# Charger_Interface_-_Relay_Controls.net
KiCad netlist of a schematic drawn in Altium Designer
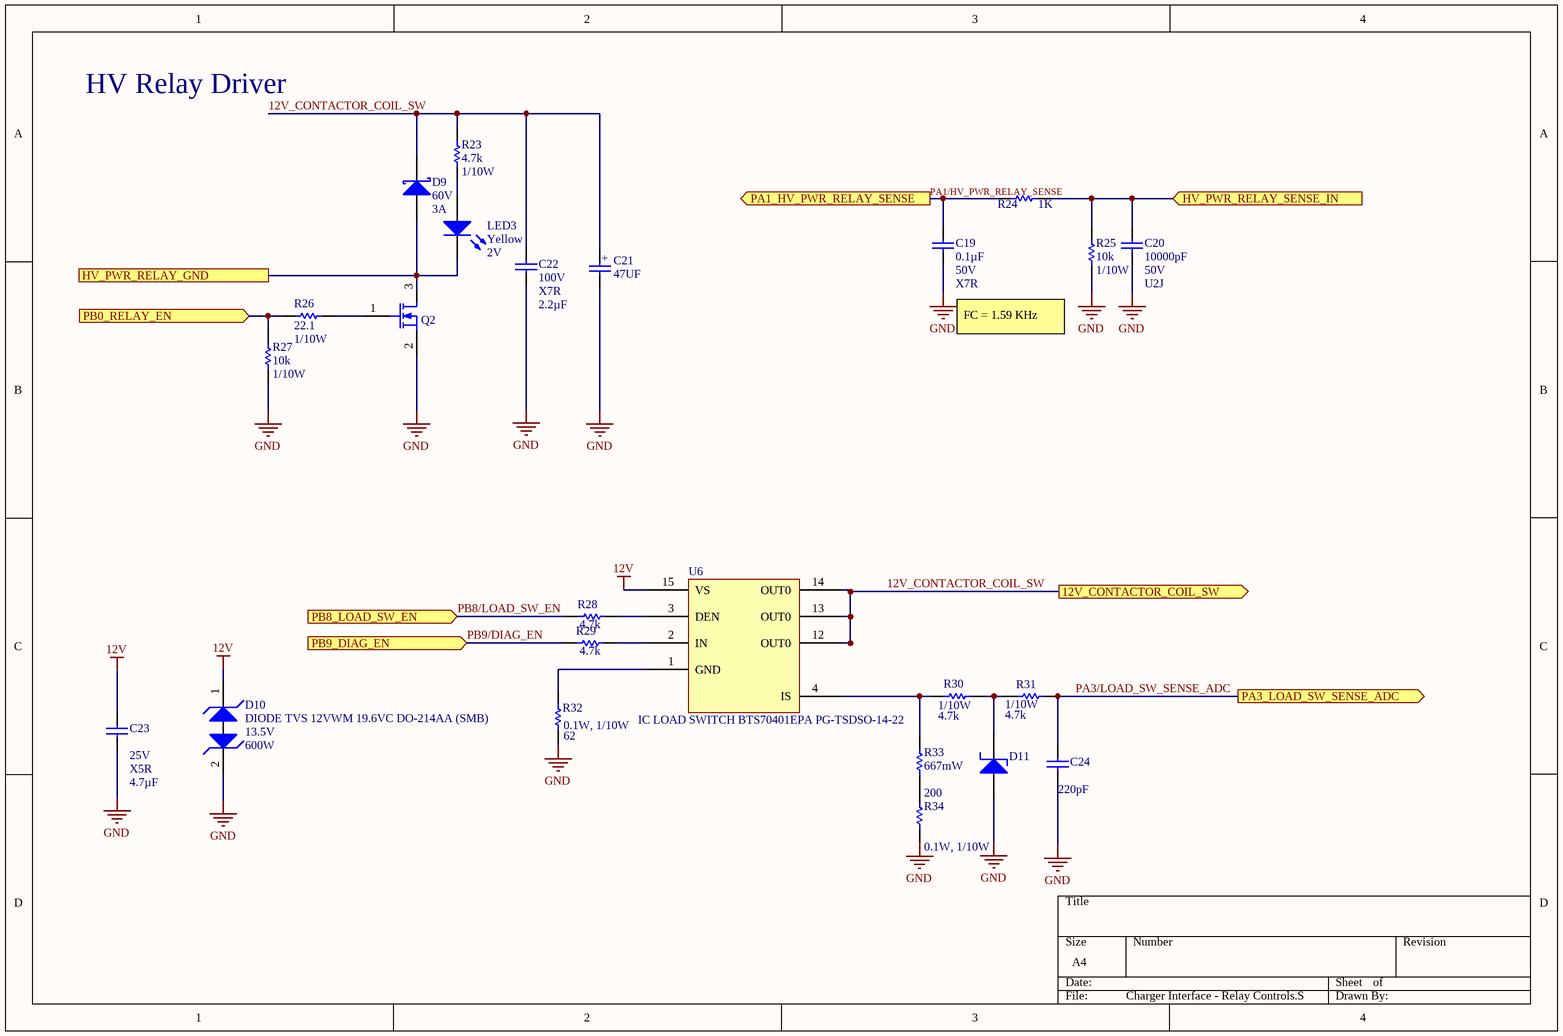
[diagram p0: Charger Interface - Relay Controls.SchDoc]

(export (version "E")
  (design (tool "Eeschema 10.0.6"))
  (components
    (comp (ref "C19")
      (value "CAP CER 0.1UF 50V 10% X7R 0603")
      (footprint "CAP, 0603")
      (description "0.10µF ±10% 50V Ceramic Capacitor X7R 0603 (1608 Metric)")
      (fields
        (field (name "TOLERANCE") "±10%")
        (field (name "CAPACITANCE") "0.1µF")
        (field (name "VOLTAGE") "50V")
        (field (name "TEMPERATURE COEFFICIENT") "X7R")
      )
      (libsource (lib "Schematic Diagrams") (part "CAP CER 0.1UF 50V 10% X7R 0603"))
    )
    (comp (ref "C20")
      (value "CAP CER 10nF 50V 5% X7R 0603")
      (footprint "CAP, 0603")
      (description "10000pF ±5% 50V Ceramic Capacitor U2J 0603 (1608 Metric)")
      (fields
        (field (name "TOLERANCE") "±5%")
        (field (name "CAPACITANCE") "10000pF")
        (field (name "VOLTAGE") "50V")
        (field (name "TEMPERATURE COEFFICIENT") "U2J")
      )
      (libsource (lib "Schematic Diagrams") (part "CAP CER 10nF 50V 5% X7R 0603"))
    )
    (comp (ref "C21")
      (value "47UF")
      (footprint "CAP ALUM 6.3MM RADIAL SMD")
      (description "47µF 35V Aluminum Electrolytic Capacitors Radial, Can - SMD 1000 Hrs @ 85°C")
      (fields (field (name "TOLERANCE") "20%") (field (name "MANUFACTURER") "Panasonic"))
      (libsource (lib "Schematic Diagrams") (part "CAP ALUM 47UF 20% 35V SMD"))
    )
    (comp (ref "C22")
      (value "2.2µF")
      (footprint "CAP, 1206")
      (description "2.2µF ±20% 100V Ceramic Capacitor X7R 1206 (3216 Metric)")
      (fields
        (field (name "VOLTAGE") "100V")
        (field (name "TEMPERATURE COEFFICIENT") "X7R")
        (field (name "TOLERANCE") "20%")
        (field (name "Comment") "CAP CER 2.2UF 100V ±20% X7R 1206")
        (field (name "SOURCE") "Schematic Diagrams.SchLib")
      )
      (libsource (lib "") (part "Symbol_2"))
    )
    (comp (ref "C23")
      (value "4.7µF")
      (footprint "CAP, 0603")
      (description "4.7µF ±10% 25V Ceramic Capacitor X5R 0603 (1608 Metric)")
      (fields
        (field (name "VOLTAGE") "25V")
        (field (name "TEMPERATURE COEFFICIENT") "X5R")
        (field (name "TOLERANCE") "10%")
        (field (name "Comment") "CAP CER 4.7UF 25V 10% X5R 0603")
        (field (name "SOURCE") "Schematic Diagrams.SchLib")
      )
      (libsource (lib "") (part "Symbol_2"))
    )
    (comp (ref "C24")
      (value "220pF")
      (footprint "CAP, 0603")
      (description "220pF ±5% 50V Ceramic Capacitor C0G, NP0 0603 (1608 Metric)")
      (fields
        (field (name "MANUFACTURER PART NUMBER") "C0603C221J5GACAUTO")
        (field (name "TOLERANCE") "5%")
        (field (name "SOURCE") "Schematic Diagrams.SchLib")
      )
      (libsource (lib "") (part "Symbol_2"))
    )
    (comp (ref "D9")
      (value "DIODE SCHOTTKY 60V 3A SMA")
      (footprint "Diode, SMA")
      (description "Diode Schottky 60V 3A Surface Mount SMA")
      (fields
        (field (name "VOLTAGE - DC REVERSE (VR) (MAX)") "60V")
        (field (name "CURRENT - AVERAGE RECTIFIED (IO)") "3A")
      )
      (libsource (lib "Schematic Diagrams") (part "DIODE SCHOTTKY 60V 3A SMA"))
    )
    (comp (ref "D10")
      (value "DIODE TVS 12VWM 19.6VC DO-214AA (SMB)")
      (footprint "DO-214AA Diode")
      (description "TVS DIODE 12V 19.6V DO214AA")
      (fields
        (field (name "VOLTAGE - BREAKDOWN (MIN)") "13.5V")
        (field (name "POWER - PEAK PULSE") "600W")
        (field (name "MANUFACTURER PART NUMBER") "SMBJ12CD-M3/H")
        (field (name "MANUFACTURER") "Vishay Semiconductor Diodes Division")
        (field (name "SOURCE") "Schematic Diagrams.SchLib")
      )
      (libsource (lib "") (part "Symbol_3"))
    )
    (comp (ref "D11")
      (value "DIODE ZENER 3.3V 200MW SOD323")
      (footprint "sod-323")
      (description "Zener Diode 3.3V 200mW ±5% Surface Mount SOD-323")
      (fields (field (name "VOLTAGE") "3.3V") (field (name "SOURCE") "Schematic Diagrams.SchLib"))
      (libsource (lib "") (part "Symbol_1"))
    )
    (comp (ref "LED3")
      (value "LED YELLOW CLEAR 2.1V 0603")
      (footprint "LED_0603")
      (description "Yellow 590nm LED Indication - Discrete 2V 0603 (1608 Metric)")
      (fields
        (field (name "MANUFACTURER") "Wurth Electronics Inc.")
        (field (name "MANUFACTURER PART NUMBER") "150060YS75000")
        (field (name "COLOR") "Yellow")
        (field (name "VOLTAGE - FORWARD (VF) (TYP)") "2V")
      )
      (libsource (lib "Schematic Diagrams") (part "LED YELLOW CLEAR 2.1V 0603"))
    )
    (comp (ref "Q2")
      (value "MOSFET N-CH 30V 6.2A 0.9W SOT-23")
      (footprint "MOSFET N-CH 30V 6.2A 0.9W SOT-23")
      (description "N-Channel 30V 6.2A (Ta) 900mW (Ta) Surface Mount SOT-23")
      (fields (field (name "MANUFACTURER") "Diodes") (field (name "MANUFACTURER PART NUMBER") "DMN3023L-7"))
      (libsource (lib "Schematic Diagrams") (part "MOSFET N-CH 30V 6.2A 0.9W SOT-23"))
    )
    (comp (ref "R23")
      (value "RES 4.7K OHM 1% 1/10W 0603")
      (footprint "RES, 0603")
      (description "4.7k Ohm ±1% 0.1W, 1/10W Chip Resistor 0603 (1608 Metric) Moisture Resistant Thick Film")
      (fields
        (field (name "TOLERANCE") "±1%")
        (field (name "RESISTANCE (OHMS)") "4.7k")
        (field (name "POWER (WATTS)") "1/10W")
      )
      (libsource (lib "Schematic Diagrams") (part "RES 4.7K OHM 1% 1/10W 0603"))
    )
    (comp (ref "R24")
      (value "1K")
      (footprint "RES, 0603")
      (description "1k Ohm ±5% 0.1W, 1/10W Chip Resistor 0603 (1608 Metric)")
      (fields
        (field (name "MANUFACTURER") "Yageo")
        (field (name "MANUFACTURER PART NUMBER") "RC0603JR-071KL")
      )
      (libsource (lib "Schematic Diagrams") (part "RES 1K OHM 5% 1/10W 0603"))
    )
    (comp (ref "R25")
      (value "RES 10K OHM 1% 1/10W 0603")
      (footprint "RES, 0603")
      (description "RES SMD 10K OHM 1% 1/10W 0603")
      (fields
        (field (name "TOLERANCE") "±1%")
        (field (name "RESISTANCE") "10k")
        (field (name "POWER") "1/10W")
      )
      (libsource (lib "Schematic Diagrams") (part "RES 10K OHM 1% 1/10W 0603"))
    )
    (comp (ref "R26")
      (value "RES 22.1 OHM 1% 1/10W 0603")
      (footprint "RES, 0603")
      (description "22.1 Ohm ±1% 0.1W, 1/10W Chip Resistor 0603 (1608 Metric) Moisture Resistant Thick Film")
      (fields
        (field (name "TOLERANCE") "±1%")
        (field (name "RESISTANCE") "22.1")
        (field (name "POWER") "1/10W")
      )
      (libsource (lib "Schematic Diagrams") (part "RES 22.1 OHM 1% 1/10W 0603"))
    )
    (comp (ref "R27")
      (value "RES 10K OHM 1% 1/10W 0603")
      (footprint "RES, 0603")
      (description "RES SMD 10K OHM 1% 1/10W 0603")
      (fields
        (field (name "TOLERANCE") "±1%")
        (field (name "RESISTANCE") "10k")
        (field (name "POWER") "1/10W")
      )
      (libsource (lib "Schematic Diagrams") (part "RES 10K OHM 1% 1/10W 0603"))
    )
    (comp (ref "R28")
      (value "RES 4.7K OHM 1% 1/10W 0603")
      (footprint "RES, 0603")
      (description "4.7k Ohm ±1% 0.1W, 1/10W Chip Resistor 0603 (1608 Metric) Moisture Resistant Thick Film")
      (fields
        (field (name "RESISTANCE (OHMS)") "4.7k")
        (field (name "TOLERANCE") "1%")
        (field (name "SOURCE") "Schematic Diagrams.SchLib")
      )
      (libsource (lib "University of Waterloo - Solar Car Team") (part "Symbol"))
    )
    (comp (ref "R29")
      (value "RES 4.7K OHM 1% 1/10W 0603")
      (footprint "RES, 0603")
      (description "4.7k Ohm ±1% 0.1W, 1/10W Chip Resistor 0603 (1608 Metric) Moisture Resistant Thick Film")
      (fields
        (field (name "RESISTANCE (OHMS)") "4.7k")
        (field (name "TOLERANCE") "1%")
        (field (name "SOURCE") "Schematic Diagrams.SchLib")
      )
      (libsource (lib "University of Waterloo - Solar Car Team") (part "Symbol"))
    )
    (comp (ref "R30")
      (value "RES 4.7K OHM 1% 1/10W 0603")
      (footprint "RES, 0603")
      (description "4.7k Ohm ±1% 0.1W, 1/10W Chip Resistor 0603 (1608 Metric) Moisture Resistant Thick Film")
      (fields
        (field (name "RESISTANCE (OHMS)") "4.7k")
        (field (name "POWER (WATTS)") "1/10W")
        (field (name "TOLERANCE") "1%")
        (field (name "SOURCE") "Schematic Diagrams.SchLib")
      )
      (libsource (lib "University of Waterloo - Solar Car Team") (part "Symbol"))
    )
    (comp (ref "R31")
      (value "RES 4.7K OHM 1% 1/10W 0603")
      (footprint "RES, 0603")
      (description "4.7k Ohm ±1% 0.1W, 1/10W Chip Resistor 0603 (1608 Metric) Moisture Resistant Thick Film")
      (fields
        (field (name "RESISTANCE (OHMS)") "4.7k")
        (field (name "POWER (WATTS)") "1/10W")
        (field (name "TOLERANCE") "1%")
        (field (name "SOURCE") "Schematic Diagrams.SchLib")
      )
      (libsource (lib "University of Waterloo - Solar Car Team") (part "Symbol"))
    )
    (comp (ref "R32")
      (value "62")
      (footprint "RES, 0603")
      (description "62 Ohms ±0.1% 0.1W, 1/10W Chip Resistor 0603 (1608 Metric) Automotive AEC-Q200 Thin Film")
      (fields
        (field (name "POWER (WATTS)") "0.1W, 1/10W")
        (field (name "MANUFACTURER PART NUMBER") "ERA-3AEB620V")
        (field (name "MANUFACTURER") "Panasonic Electronic Components")
        (field (name "SOURCE") "Schematic Diagrams.SchLib")
      )
      (libsource (lib "University of Waterloo - Solar Car Team") (part "Symbol"))
    )
    (comp (ref "R33")
      (value "200")
      (footprint "RES 1206")
      (fields
        (field (name "MAX POWER DISSIPATION") "667mW")
        (field (name "TOLERANCE") "5%")
        (field (name "MANUFACTURER PART NUMBER") "ERJ-P08J201V")
        (field (name "MANUFACTURER") "Panasonic")
        (field (name "SOURCE") "Schematic Diagrams.SchLib")
      )
      (libsource (lib "University of Waterloo - Solar Car Team") (part "Symbol"))
    )
    (comp (ref "R34")
      (value "RES 1K OHM 5% 1/10W 0603")
      (footprint "RES, 0603")
      (description "1k Ohm ±5% 0.1W, 1/10W Chip Resistor 0603 (1608 Metric)")
      (fields
        (field (name "TOLERANCE") "5%")
        (field (name "POWER (WATTS)") "0.1W, 1/10W")
        (field (name "MANUFACTURER") "Yageo")
        (field (name "SOURCE") "Schematic Diagrams.SchLib")
      )
      (libsource (lib "University of Waterloo - Solar Car Team") (part "Symbol"))
    )
    (comp (ref "U6")
      (value "IC LOAD SWITCH BTS70401EPA PG-TSDSO-14-22")
      (footprint "IC LOAD SWITCH PG-TSDSO-14-22")
      (description "Power Switch/Driver 1:1 N-Channel 4.5A PG-TSDSO-14-22")
      (fields
        (field (name "MANUFACTURER") "Infineon")
        (field (name "MANUFACTURER PART NUMBER") "BTS70401EPAXUMA1")
        (field (name "SOURCE") "Schematic Diagrams.SchLib")
      )
      (libsource (lib "University of Waterloo - Solar Car Team") (part "IC LOAD SWITCH BTS70401EPA PG-TSDSO-14-22"))
    )
  )
  (nets
    (net (code "1") (name "/12V_CONTACTOR_COIL_SW") (class "Default")
      (node (ref "C21") (pin "1") (pinfunction "1_1") (pintype "passive"))
      (node (ref "C22") (pin "1") (pinfunction "1_1") (pintype "passive"))
      (node (ref "D9") (pin "2") (pinfunction "2_2") (pintype "passive"))
      (node (ref "R23") (pin "1") (pinfunction "1_1") (pintype "passive"))
      (node (ref "U6") (pin "12") (pinfunction "OUT0_12") (pintype "passive"))
      (node (ref "U6") (pin "13") (pinfunction "OUT0_13") (pintype "passive"))
      (node (ref "U6") (pin "14") (pinfunction "OUT0_14") (pintype "passive"))
    )
    (net (code "2") (name "/HV_PWR_RELAY_GND") (class "Default")
      (node (ref "D9") (pin "1") (pinfunction "1_1") (pintype "passive"))
      (node (ref "LED3") (pin "2") (pinfunction "K_2") (pintype "passive"))
      (node (ref "Q2") (pin "3") (pinfunction "D_3") (pintype "passive"))
    )
    (net (code "3") (name "/HV_PWR_RELAY_SENSE_IN") (class "Default")
      (node (ref "C20") (pin "1") (pinfunction "1_1") (pintype "passive"))
      (node (ref "R24") (pin "2") (pinfunction "2_2") (pintype "passive"))
      (node (ref "R25") (pin "1") (pinfunction "1_1") (pintype "passive"))
    )
    (net (code "4") (name "/PA1{slash}HV_PWR_RELAY_SENSE") (class "Default")
      (node (ref "C19") (pin "1") (pinfunction "1_1") (pintype "passive"))
      (node (ref "R24") (pin "1") (pinfunction "1_1") (pintype "passive"))
    )
    (net (code "5") (name "/PA3{slash}LOAD_SW_SENSE_ADC") (class "Default")
      (node (ref "C24") (pin "1") (pinfunction "1_1") (pintype "passive"))
      (node (ref "R31") (pin "2") (pinfunction "2_2") (pintype "passive"))
    )
    (net (code "6") (name "/PB0_RELAY_EN") (class "Default")
      (node (ref "R26") (pin "1") (pinfunction "1_1") (pintype "passive"))
      (node (ref "R27") (pin "1") (pinfunction "1_1") (pintype "passive"))
    )
    (net (code "7") (name "/PB8{slash}LOAD_SW_EN") (class "Default")
      (node (ref "R28") (pin "2") (pinfunction "2_2") (pintype "passive"))
    )
    (net (code "8") (name "/PB9{slash}DIAG_EN") (class "Default")
      (node (ref "R29") (pin "2") (pinfunction "2_2") (pintype "passive"))
    )
    (net (code "9") (name "12V") (class "Default")
      (node (ref "C23") (pin "1") (pinfunction "1_1") (pintype "passive"))
      (node (ref "D10") (pin "1") (pinfunction "Cathode1_1") (pintype "passive"))
      (node (ref "U6") (pin "15") (pinfunction "VS_15") (pintype "passive"))
    )
    (net (code "10") (name "GND") (class "Default")
      (node (ref "C19") (pin "2") (pinfunction "2_2") (pintype "passive"))
      (node (ref "C20") (pin "2") (pinfunction "2_2") (pintype "passive"))
      (node (ref "C21") (pin "2") (pinfunction "2_2") (pintype "passive"))
      (node (ref "C22") (pin "2") (pinfunction "2_2") (pintype "passive"))
      (node (ref "C23") (pin "2") (pinfunction "2_2") (pintype "passive"))
      (node (ref "C24") (pin "2") (pinfunction "2_2") (pintype "passive"))
      (node (ref "D10") (pin "2") (pinfunction "Cathode2_2") (pintype "passive"))
      (node (ref "D11") (pin "1") (pinfunction "A_1") (pintype "passive"))
      (node (ref "Q2") (pin "2") (pinfunction "S_2") (pintype "passive"))
      (node (ref "R25") (pin "2") (pinfunction "2_2") (pintype "passive"))
      (node (ref "R27") (pin "2") (pinfunction "2_2") (pintype "passive"))
      (node (ref "R32") (pin "2") (pinfunction "2_2") (pintype "passive"))
      (node (ref "R34") (pin "2") (pinfunction "2_2") (pintype "passive"))
    )
    (net (code "11") (name "Net-(D11-K)") (class "Default")
      (node (ref "D11") (pin "2") (pinfunction "K_2") (pintype "passive"))
      (node (ref "R30") (pin "2") (pinfunction "2_2") (pintype "passive"))
      (node (ref "R31") (pin "1") (pinfunction "1_1") (pintype "passive"))
    )
    (net (code "12") (name "Net-(LED3-A)") (class "Default")
      (node (ref "LED3") (pin "1") (pinfunction "A_1") (pintype "passive"))
      (node (ref "R23") (pin "2") (pinfunction "2_2") (pintype "passive"))
    )
    (net (code "13") (name "Net-(Q2-G)") (class "Default")
      (node (ref "Q2") (pin "1") (pinfunction "G_1") (pintype "passive"))
      (node (ref "R26") (pin "2") (pinfunction "2_2") (pintype "passive"))
    )
    (net (code "14") (name "Net-(R33-Pad2)") (class "Default")
      (node (ref "R33") (pin "2") (pinfunction "2_2") (pintype "passive"))
      (node (ref "R34") (pin "1") (pinfunction "1_1") (pintype "passive"))
    )
    (net (code "15") (name "Net-(U6-DEN)") (class "Default")
      (node (ref "R28") (pin "1") (pinfunction "1_1") (pintype "passive"))
      (node (ref "U6") (pin "3") (pinfunction "DEN_3") (pintype "passive"))
    )
    (net (code "16") (name "Net-(U6-GND)") (class "Default")
      (node (ref "R32") (pin "1") (pinfunction "1_1") (pintype "passive"))
      (node (ref "U6") (pin "1") (pinfunction "GND_1") (pintype "passive"))
    )
    (net (code "17") (name "Net-(U6-IN)") (class "Default")
      (node (ref "R29") (pin "1") (pinfunction "1_1") (pintype "passive"))
      (node (ref "U6") (pin "2") (pinfunction "IN_2") (pintype "passive"))
    )
    (net (code "18") (name "Net-(U6-IS)") (class "Default")
      (node (ref "R30") (pin "1") (pinfunction "1_1") (pintype "passive"))
      (node (ref "R33") (pin "1") (pinfunction "1_1") (pintype "passive"))
      (node (ref "U6") (pin "4") (pinfunction "IS_4") (pintype "passive"))
    )
  )
)
